# LNA.net
KiCad netlist of a schematic drawn in Altium Designer
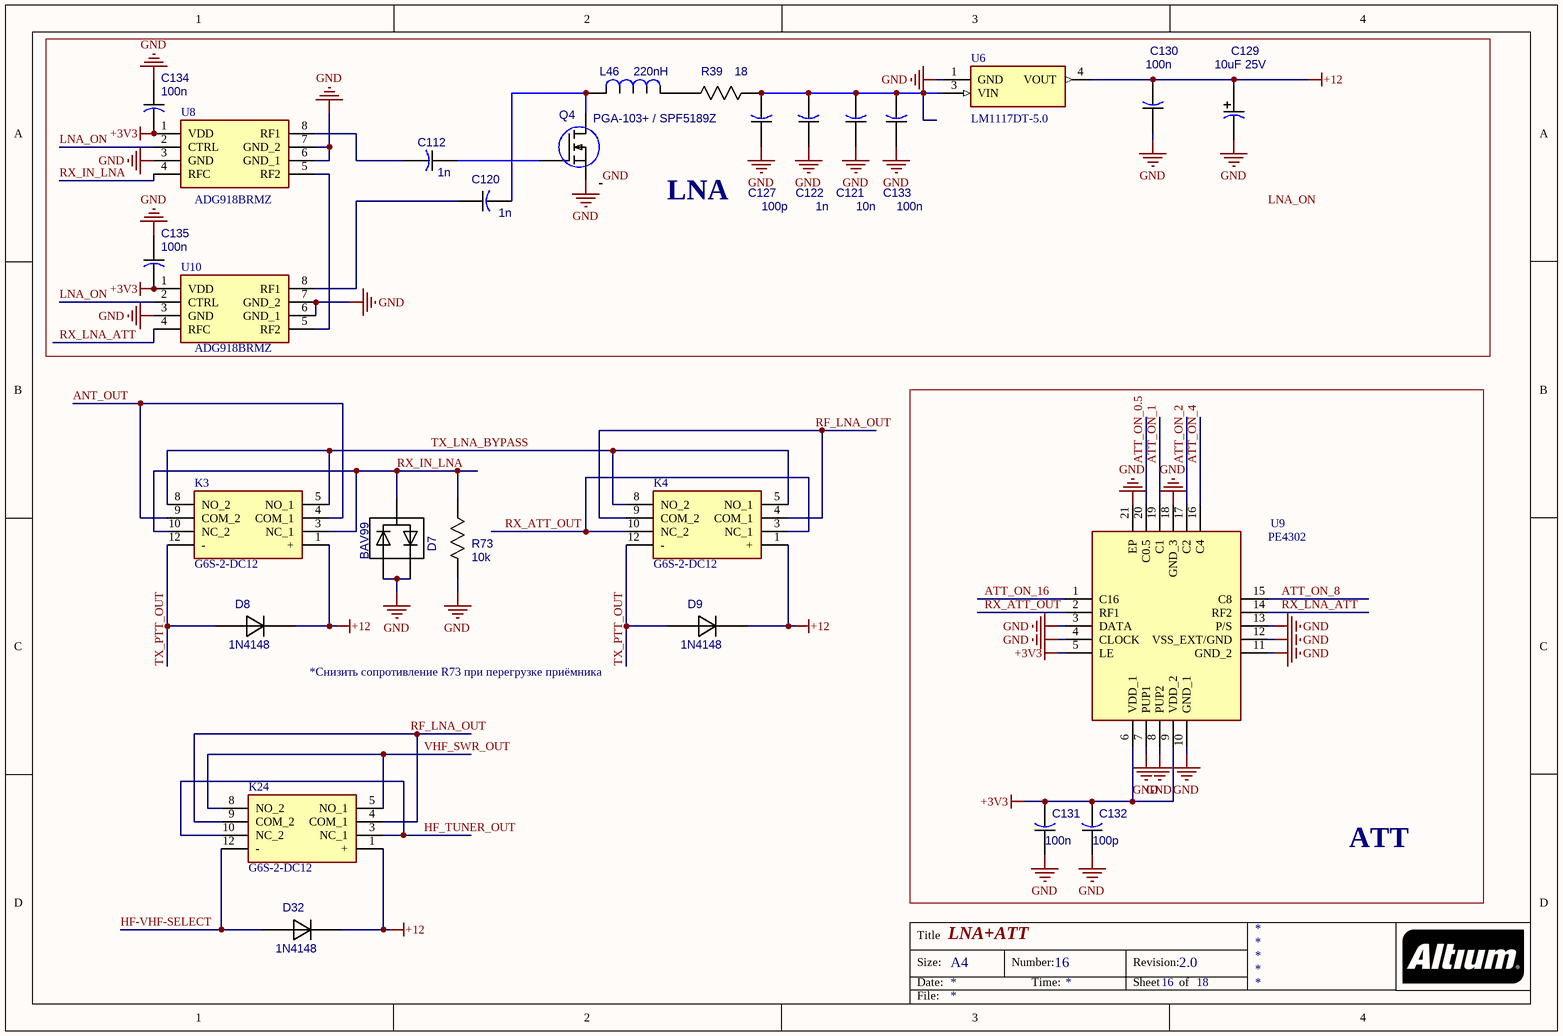
[diagram p0: LNA.SchDoc]

(export (version "E")
  (design (tool "Eeschema 10.0.6"))
  (components
    (comp (ref "C112")
      (value "1n")
      (footprint "CAP_0805")
      (description "CAP_0805")
      (libsource (lib "") (part "CAP_0805_1"))
    )
    (comp (ref "C120")
      (value "1n")
      (footprint "CAP_0805")
      (description "CAP_0805")
      (libsource (lib "") (part "CAP_0805_1"))
    )
    (comp (ref "C121")
      (value "10n")
      (footprint "6-0805_M")
      (description "CAP_0805")
      (libsource (lib "") (part "CAP_0805_1"))
    )
    (comp (ref "C122")
      (value "1n")
      (footprint "6-0805_M")
      (description "CAP_0805")
      (libsource (lib "") (part "CAP_0805_1"))
    )
    (comp (ref "C127")
      (value "100p")
      (footprint "6-0805_M")
      (description "CAP_0805")
      (libsource (lib "") (part "CAP_0805_1"))
    )
    (comp (ref "C129")
      (value "10uF 25V")
      (footprint "CAPAE_5.3x5.3h6.1")
      (description "CAPAE_5.3x5.3h6.1")
      (libsource (lib "*") (part "CAPAE_5.3x5.3h6.1"))
    )
    (comp (ref "C130")
      (value "100n")
      (footprint "CAP_0805")
      (description "CAP_0805")
      (libsource (lib "*") (part "CAP_0805"))
    )
    (comp (ref "C131")
      (value "100n")
      (footprint "6-0805_M")
      (description "CAP_0805")
      (libsource (lib "") (part "CAP_0805_1"))
    )
    (comp (ref "C132")
      (value "100p")
      (footprint "6-0805_M")
      (description "CAP_0805")
      (libsource (lib "") (part "CAP_0805_1"))
    )
    (comp (ref "C133")
      (value "100n")
      (footprint "CAP_0805")
      (description "CAP_0805")
      (libsource (lib "") (part "CAP_0805_1"))
    )
    (comp (ref "C134")
      (value "100n")
      (footprint "CAP_0805")
      (description "CAP_0805")
      (libsource (lib "") (part "CAP_0805_1"))
    )
    (comp (ref "C135")
      (value "100n")
      (footprint "CAP_0805")
      (description "CAP_0805")
      (libsource (lib "") (part "CAP_0805_1"))
    )
    (comp (ref "D7") (value "BAV99") (footprint "SOT23") (libsource (lib "*") (part "BAV99")))
    (comp (ref "D8") (value "1N4148") (footprint "SS14") (libsource (lib "RF-UNIT-BIG") (part "1N4148")))
    (comp (ref "D9") (value "1N4148") (footprint "SS14") (libsource (lib "RF-UNIT-BIG") (part "1N4148")))
    (comp (ref "D32") (value "1N4148") (footprint "SS14") (libsource (lib "RF-UNIT-BIG") (part "1N4148")))
    (comp (ref "K3")
      (value "G6S-2-DC12")
      (footprint "SamacSys:G6S2DC12")
      (description "Relay or Contactor")
      (fields (field (name "MOUSER PART NUMBER") "653-G6S-2-DC12A"))
      (libsource (lib "*") (part "G6S-2-DC12"))
    )
    (comp (ref "K4")
      (value "G6S-2-DC12")
      (footprint "SamacSys:G6S2DC12")
      (description "Relay or Contactor")
      (fields (field (name "MOUSER PART NUMBER") "653-G6S-2-DC12A"))
      (libsource (lib "*") (part "G6S-2-DC12"))
    )
    (comp (ref "K24")
      (value "G6S-2-DC12")
      (footprint "SamacSys:G6S2DC12")
      (description "Relay or Contactor")
      (fields (field (name "MOUSER PART NUMBER") "653-G6S-2-DC12A"))
      (libsource (lib "*") (part "G6S-2-DC12"))
    )
    (comp (ref "L46")
      (value "220nH")
      (footprint "IND_1206")
      (description "IND_1206")
      (libsource (lib "*") (part "IND_1206"))
    )
    (comp (ref "Q4")
      (value "PGA-103+ / SPF5189Z")
      (footprint "SOT89")
      (libsource (lib "*") (part "PGA-103+"))
    )
    (comp (ref "R39")
      (value "18")
      (footprint "RES_1206")
      (description "RES_1206")
      (libsource (lib "*") (part "RES_1206"))
    )
    (comp (ref "R73")
      (value "10k")
      (footprint "RES_1206")
      (description "RES_1206")
      (libsource (lib "*") (part "RES_1206"))
    )
    (comp (ref "U6")
      (value "LM1117DT-5.0")
      (footprint "SamacSys:TO228P991X238-3N")
      (description "Integrated Circuit")
      (fields
        (field (name "MANUFACTURER_PART_NUMBER") "LM1117DT-ADJ")
        (field (name "MOUSER PART NUMBER") "926-LM1117DT-ADJ")
      )
      (libsource (lib "*") (part "LM1117DT-ADJ"))
    )
    (comp (ref "U8")
      (value "ADG918BRMZ")
      (footprint "SOP65P490X110-8N")
      (description "Integrated Circuit")
      (fields (field (name "MOUSER PART NUMBER") "584-ADG918BRMZ") (field (name "RS PART NUMBER") "4969212P"))
      (libsource (lib "RF-UNIT-BIG") (part "ADG918BRMZ"))
    )
    (comp (ref "U9")
      (value "PE4302")
      (footprint "QFN50P400X400X90-21N")
      (description "Integrated Circuit")
      (fields (field (name "MANUFACTURER_PART_NUMBER") "PE4312C-Z"))
      (libsource (lib "RF-UNIT-BIG") (part "PE4312C-Z"))
    )
    (comp (ref "U10")
      (value "ADG918BRMZ")
      (footprint "SOP65P490X110-8N")
      (description "Integrated Circuit")
      (fields (field (name "MOUSER PART NUMBER") "584-ADG918BRMZ") (field (name "RS PART NUMBER") "4969212P"))
      (libsource (lib "RF-UNIT-BIG") (part "ADG918BRMZ"))
    )
  )
  (nets
    (net (code "1") (name "+3V3") (class "Default")
      (node (ref "C131") (pin "2") (pinfunction "2_2") (pintype "passive"))
      (node (ref "C132") (pin "2") (pinfunction "2_2") (pintype "passive"))
      (node (ref "C134") (pin "2") (pinfunction "2_2") (pintype "passive"))
      (node (ref "C135") (pin "2") (pinfunction "2_2") (pintype "passive"))
      (node (ref "U10") (pin "1") (pinfunction "VDD_1") (pintype "power_in"))
      (node (ref "U8") (pin "1") (pinfunction "VDD_1") (pintype "power_in"))
      (node (ref "U9") (pin "5") (pinfunction "LE_5") (pintype "passive"))
      (node (ref "U9") (pin "6") (pinfunction "VDD_1_6") (pintype "passive"))
      (node (ref "U9") (pin "9") (pinfunction "VDD_2_9") (pintype "passive"))
    )
    (net (code "2") (name "+12") (class "Default")
      (node (ref "C129") (pin "1") (pinfunction "PLUS_1") (pintype "passive"))
      (node (ref "C130") (pin "2") (pinfunction "2_2") (pintype "passive"))
      (node (ref "D32") (pin "1") (pinfunction "K_1") (pintype "passive"))
      (node (ref "D8") (pin "1") (pinfunction "K_1") (pintype "passive"))
      (node (ref "D9") (pin "1") (pinfunction "K_1") (pintype "passive"))
      (node (ref "K24") (pin "1") (pinfunction "+_1") (pintype "passive"))
      (node (ref "K3") (pin "1") (pinfunction "+_1") (pintype "passive"))
      (node (ref "K4") (pin "1") (pinfunction "+_1") (pintype "passive"))
      (node (ref "U6") (pin "4") (pinfunction "VOUT_4") (pintype "output"))
    )
    (net (code "3") (name "/ANT_OUT") (class "Default")
      (node (ref "K3") (pin "4") (pinfunction "COM_1_4") (pintype "passive"))
      (node (ref "K3") (pin "9") (pinfunction "COM_2_9") (pintype "passive"))
    )
    (net (code "4") (name "/ATT_ON_0.5") (class "Default")
      (node (ref "U9") (pin "20") (pinfunction "C0.5_20") (pintype "passive"))
    )
    (net (code "5") (name "/ATT_ON_1") (class "Default")
      (node (ref "U9") (pin "19") (pinfunction "C1_19") (pintype "passive"))
    )
    (net (code "6") (name "/ATT_ON_2") (class "Default")
      (node (ref "U9") (pin "17") (pinfunction "C2_17") (pintype "passive"))
    )
    (net (code "7") (name "/ATT_ON_4") (class "Default")
      (node (ref "U9") (pin "16") (pinfunction "C4_16") (pintype "passive"))
    )
    (net (code "8") (name "/ATT_ON_8") (class "Default")
      (node (ref "U9") (pin "15") (pinfunction "C8_15") (pintype "passive"))
    )
    (net (code "9") (name "/ATT_ON_16") (class "Default")
      (node (ref "U9") (pin "1") (pinfunction "C16_1") (pintype "passive"))
    )
    (net (code "10") (name "/HF-VHF-SELECT") (class "Default")
      (node (ref "D32") (pin "2") (pinfunction "A_2") (pintype "passive"))
      (node (ref "K24") (pin "12") (pinfunction "-_12") (pintype "passive"))
    )
    (net (code "11") (name "/HF_TUNER_OUT") (class "Default")
      (node (ref "K24") (pin "10") (pinfunction "NC_2_10") (pintype "passive"))
      (node (ref "K24") (pin "3") (pinfunction "NC_1_3") (pintype "passive"))
    )
    (net (code "12") (name "/LNA_ON") (class "Default")
      (node (ref "U10") (pin "2") (pinfunction "CTRL_2") (pintype "passive"))
      (node (ref "U8") (pin "2") (pinfunction "CTRL_2") (pintype "passive"))
    )
    (net (code "13") (name "/RF_LNA_OUT") (class "Default")
      (node (ref "K24") (pin "4") (pinfunction "COM_1_4") (pintype "passive"))
      (node (ref "K24") (pin "9") (pinfunction "COM_2_9") (pintype "passive"))
      (node (ref "K4") (pin "4") (pinfunction "COM_1_4") (pintype "passive"))
      (node (ref "K4") (pin "9") (pinfunction "COM_2_9") (pintype "passive"))
    )
    (net (code "14") (name "/RX_ATT_OUT") (class "Default")
      (node (ref "K4") (pin "10") (pinfunction "NC_2_10") (pintype "passive"))
      (node (ref "K4") (pin "3") (pinfunction "NC_1_3") (pintype "passive"))
      (node (ref "U9") (pin "2") (pinfunction "RF1_2") (pintype "passive"))
    )
    (net (code "15") (name "/RX_IN_LNA") (class "Default")
      (node (ref "D7") (pin "3") (pinfunction "C(D1),A(D2)_3") (pintype "passive"))
      (node (ref "K3") (pin "10") (pinfunction "NC_2_10") (pintype "passive"))
      (node (ref "K3") (pin "3") (pinfunction "NC_1_3") (pintype "passive"))
      (node (ref "R73") (pin "2") (pinfunction "2_2") (pintype "passive"))
      (node (ref "U8") (pin "4") (pinfunction "RFC_4") (pintype "passive"))
    )
    (net (code "16") (name "/RX_LNA_ATT") (class "Default")
      (node (ref "U10") (pin "4") (pinfunction "RFC_4") (pintype "passive"))
      (node (ref "U9") (pin "14") (pinfunction "RF2_14") (pintype "passive"))
    )
    (net (code "17") (name "/TX_LNA_BYPASS") (class "Default")
      (node (ref "K3") (pin "5") (pinfunction "NO_1_5") (pintype "passive"))
      (node (ref "K3") (pin "8") (pinfunction "NO_2_8") (pintype "passive"))
      (node (ref "K4") (pin "5") (pinfunction "NO_1_5") (pintype "passive"))
      (node (ref "K4") (pin "8") (pinfunction "NO_2_8") (pintype "passive"))
    )
    (net (code "18") (name "/TX_PTT_OUT") (class "Default")
      (node (ref "D8") (pin "2") (pinfunction "A_2") (pintype "passive"))
      (node (ref "D9") (pin "2") (pinfunction "A_2") (pintype "passive"))
      (node (ref "K3") (pin "12") (pinfunction "-_12") (pintype "passive"))
      (node (ref "K4") (pin "12") (pinfunction "-_12") (pintype "passive"))
    )
    (net (code "19") (name "/VHF_SWR_OUT") (class "Default")
      (node (ref "K24") (pin "5") (pinfunction "NO_1_5") (pintype "passive"))
      (node (ref "K24") (pin "8") (pinfunction "NO_2_8") (pintype "passive"))
    )
    (net (code "20") (name "GND") (class "Default")
      (node (ref "C121") (pin "1") (pinfunction "1_1") (pintype "passive"))
      (node (ref "C122") (pin "1") (pinfunction "1_1") (pintype "passive"))
      (node (ref "C127") (pin "1") (pinfunction "1_1") (pintype "passive"))
      (node (ref "C129") (pin "2") (pinfunction "MINUS_2") (pintype "passive"))
      (node (ref "C130") (pin "1") (pinfunction "1_1") (pintype "passive"))
      (node (ref "C131") (pin "1") (pinfunction "1_1") (pintype "passive"))
      (node (ref "C132") (pin "1") (pinfunction "1_1") (pintype "passive"))
      (node (ref "C133") (pin "1") (pinfunction "1_1") (pintype "passive"))
      (node (ref "C134") (pin "1") (pinfunction "1_1") (pintype "passive"))
      (node (ref "C135") (pin "1") (pinfunction "1_1") (pintype "passive"))
      (node (ref "D7") (pin "1") (pinfunction "A(D1)_1") (pintype "passive"))
      (node (ref "D7") (pin "2") (pinfunction "C(D2)_2") (pintype "passive"))
      (node (ref "Q4") (pin "0") (pinfunction "0_0") (pintype "passive"))
      (node (ref "Q4") (pin "2") (pinfunction "S_2") (pintype "passive"))
      (node (ref "R73") (pin "1") (pinfunction "1_1") (pintype "passive"))
      (node (ref "U10") (pin "3") (pinfunction "GND_3") (pintype "power_in"))
      (node (ref "U10") (pin "6") (pinfunction "GND_1_6") (pintype "power_in"))
      (node (ref "U10") (pin "7") (pinfunction "GND_2_7") (pintype "power_in"))
      (node (ref "U6") (pin "1") (pinfunction "GND_1") (pintype "passive"))
      (node (ref "U8") (pin "3") (pinfunction "GND_3") (pintype "power_in"))
      (node (ref "U8") (pin "6") (pinfunction "GND_1_6") (pintype "power_in"))
      (node (ref "U8") (pin "7") (pinfunction "GND_2_7") (pintype "power_in"))
      (node (ref "U9") (pin "10") (pinfunction "GND_1_10") (pintype "passive"))
      (node (ref "U9") (pin "11") (pinfunction "GND_2_11") (pintype "passive"))
      (node (ref "U9") (pin "12") (pinfunction "VSS_EXT/GND_12") (pintype "passive"))
      (node (ref "U9") (pin "13") (pinfunction "P/S_13") (pintype "passive"))
      (node (ref "U9") (pin "18") (pinfunction "GND_3_18") (pintype "passive"))
      (node (ref "U9") (pin "21") (pinfunction "EP_21") (pintype "passive"))
      (node (ref "U9") (pin "3") (pinfunction "DATA_3") (pintype "passive"))
      (node (ref "U9") (pin "4") (pinfunction "CLOCK_4") (pintype "passive"))
      (node (ref "U9") (pin "7") (pinfunction "PUP1_7") (pintype "passive"))
      (node (ref "U9") (pin "8") (pinfunction "PUP2_8") (pintype "passive"))
    )
    (net (code "21") (name "Net-(L46-1)") (class "Default")
      (node (ref "C120") (pin "2") (pinfunction "2_2") (pintype "passive"))
      (node (ref "L46") (pin "2") (pinfunction "1_2") (pintype "passive"))
      (node (ref "Q4") (pin "3") (pinfunction "D_3") (pintype "passive"))
    )
    (net (code "22") (name "Net-(L46-2)") (class "Default")
      (node (ref "L46") (pin "1") (pinfunction "2_1") (pintype "passive"))
      (node (ref "R39") (pin "2") (pinfunction "2_2") (pintype "passive"))
    )
    (net (code "23") (name "Net-(Q4-G)") (class "Default")
      (node (ref "C112") (pin "1") (pinfunction "1_1") (pintype "passive"))
      (node (ref "Q4") (pin "1") (pinfunction "G_1") (pintype "passive"))
    )
    (net (code "24") (name "Net-(U6-VIN)") (class "Default")
      (node (ref "C121") (pin "2") (pinfunction "2_2") (pintype "passive"))
      (node (ref "C122") (pin "2") (pinfunction "2_2") (pintype "passive"))
      (node (ref "C127") (pin "2") (pinfunction "2_2") (pintype "passive"))
      (node (ref "C133") (pin "2") (pinfunction "2_2") (pintype "passive"))
      (node (ref "R39") (pin "1") (pinfunction "1_1") (pintype "passive"))
      (node (ref "U6") (pin "3") (pinfunction "VIN_3") (pintype "input"))
    )
    (net (code "25") (name "Net-(U8-RF1)") (class "Default")
      (node (ref "C112") (pin "2") (pinfunction "2_2") (pintype "passive"))
      (node (ref "U8") (pin "8") (pinfunction "RF1_8") (pintype "passive"))
    )
    (net (code "26") (name "Net-(U10-RF1)") (class "Default")
      (node (ref "C120") (pin "1") (pinfunction "1_1") (pintype "passive"))
      (node (ref "U10") (pin "8") (pinfunction "RF1_8") (pintype "passive"))
    )
    (net (code "27") (name "Net-(U10-RF2)") (class "Default")
      (node (ref "U10") (pin "5") (pinfunction "RF2_5") (pintype "passive"))
      (node (ref "U8") (pin "5") (pinfunction "RF2_5") (pintype "passive"))
    )
  )
)
